# JadePlus_v0_3_1_schematics_PG3_CONN.net
KiCad netlist of a schematic drawn in Altium Designer
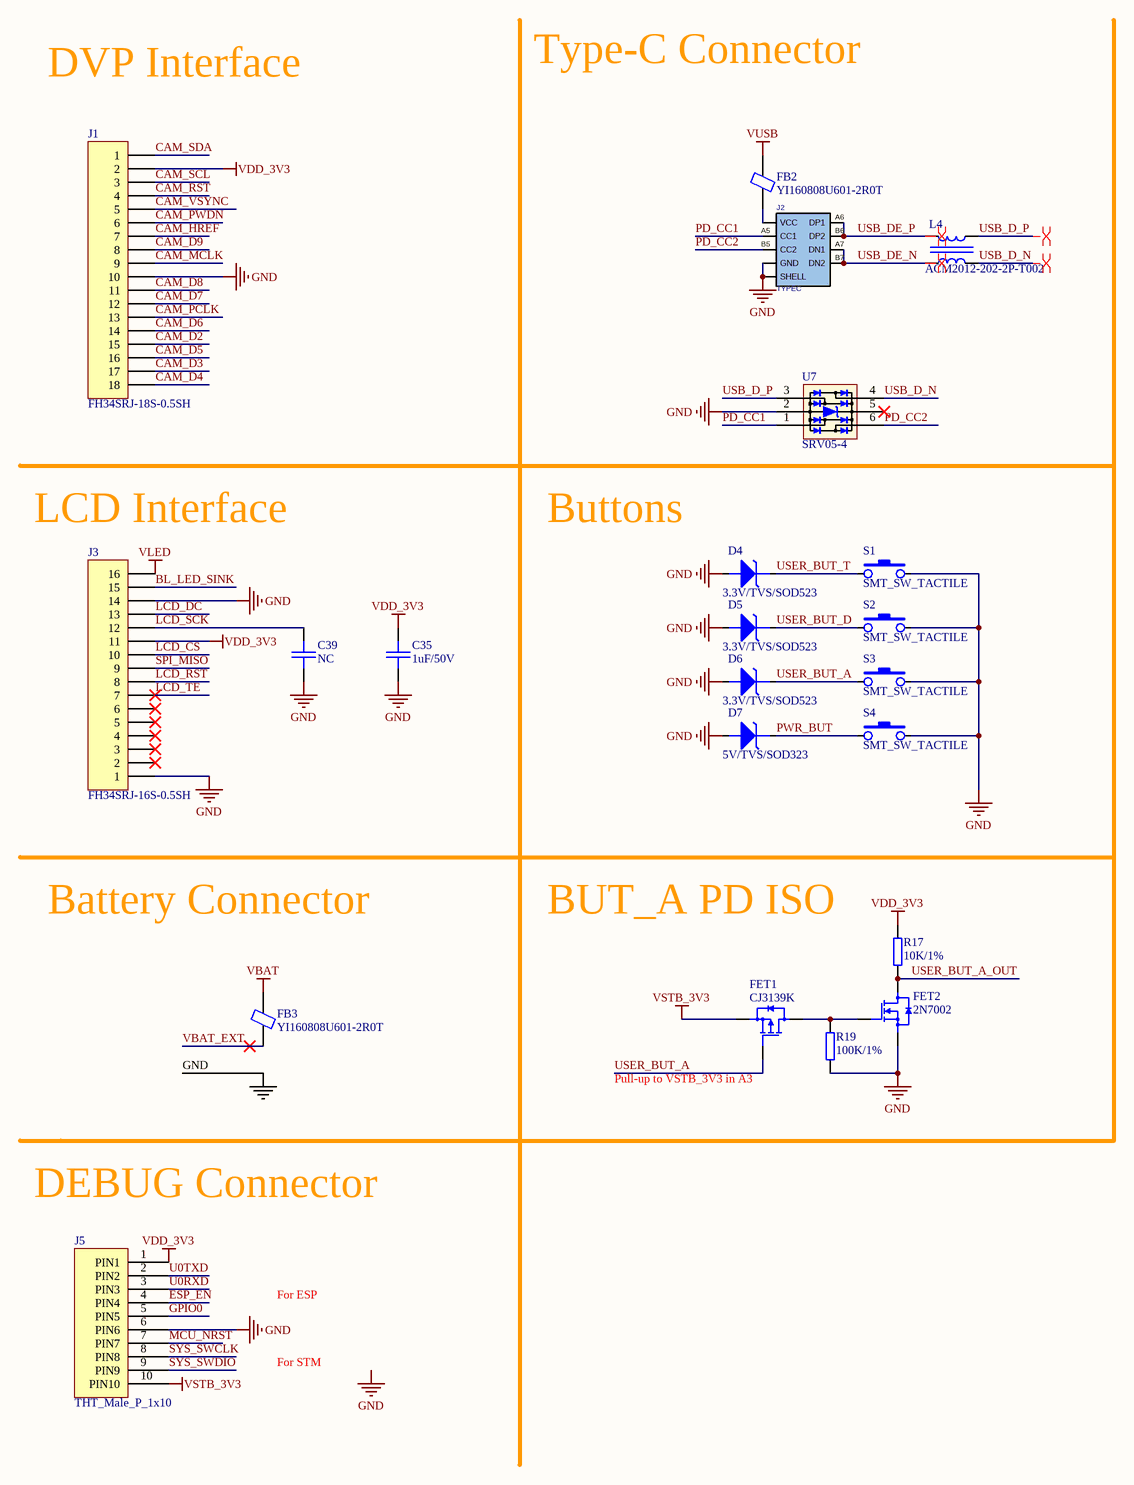
[diagram p0: JadePlus_v0.3.1_schematics_PG3_CONN.SchDoc]

(export (version "E")
  (design (tool "Eeschema 10.0.6"))
  (components
    (comp (ref "C35")
      (value "1uF/50V")
      (footprint "HD-Components:C0402-L-HD")
      (description "Surface mount capacitor 0402")
      (libsource (lib "Vowstar_Basic_Device") (part "SMT_C_0402"))
    )
    (comp (ref "C39")
      (value "NC")
      (footprint "HD-Components:C0201-HD")
      (description "Surface mount capacitor 0402")
      (libsource (lib "Vowstar_Basic_Device") (part "SMT_C_0402"))
    )
    (comp (ref "D4")
      (value "3.3V/TVS/SOD523")
      (footprint "SMT_DIODE_SOD_523")
      (description "Surface mount unidirectional TVS diode SOD-523(0603) Package")
      (libsource (lib "Vowstar_Basic_Device") (part "SMT_DIODE_TVS_U_SOD_523"))
    )
    (comp (ref "D5")
      (value "3.3V/TVS/SOD523")
      (footprint "SMT_DIODE_SOD_523")
      (description "Surface mount unidirectional TVS diode SOD-523(0603) Package")
      (libsource (lib "Vowstar_Basic_Device") (part "SMT_DIODE_TVS_U_SOD_523"))
    )
    (comp (ref "D6")
      (value "3.3V/TVS/SOD523")
      (footprint "SMT_DIODE_SOD_523")
      (description "Surface mount unidirectional TVS diode SOD-523(0603) Package")
      (libsource (lib "Vowstar_Basic_Device") (part "SMT_DIODE_TVS_U_SOD_523"))
    )
    (comp (ref "D7")
      (value "5V/TVS/SOD323")
      (footprint "SMT_DIODE_SOD_323")
      (description "Surface mount unidirectional TVS diode SOD-523(0603) Package")
      (libsource (lib "Vowstar_Basic_Device") (part "SMT_DIODE_TVS_U_SOD_523"))
    )
    (comp (ref "FB2")
      (value "YI160808U601-2R0T")
      (footprint "L0603-HD")
      (description "Surface mount ferrite beads 0603")
      (libsource (lib "Vowstar_Basic_Device") (part "SMT_FB_0603"))
    )
    (comp (ref "FB3")
      (value "YI160808U601-2R0T")
      (footprint "L0603-HD")
      (description "Surface mount ferrite beads 0603")
      (libsource (lib "Vowstar_Basic_Device") (part "SMT_FB_0603"))
    )
    (comp (ref "FET1")
      (value "CJ3139K")
      (footprint "SOT-723-HD")
      (description "SI2301-P-Ch,-2.3A, -20V.RDS(ON) = 0.190Ω @ VGS = -2.5 V")
      (libsource (lib "Vowstar_Basic_Device") (part "SI2301-P-Ch-MOSFET"))
    )
    (comp (ref "FET2")
      (value "2N7002")
      (footprint "SOT-723-HD")
      (description "SI2302-N-Ch,3A, 20V.RDS(ON) = 0.082Ω @ VGS = 2.5 V")
      (libsource (lib "Vowstar_Basic_Device") (part "SI2302-N-Ch-MOSFET"))
    )
    (comp (ref "J1")
      (value "FH34SRJ-18S-0.5SH")
      (footprint "FH34SRJ-18S-0.5SH")
      (description "Header, 18-Pin")
      (fields (field (name "PUBLISHER") "Altium Limited"))
      (libsource (lib "Miscellaneous Connectors") (part "Header 18"))
    )
    (comp (ref "J2")
      (value "TYPEC")
      (footprint "USB_TYPEC_16P_HD")
      (libsource (lib "LibMySelf_SCHLIB") (part "USB_TYPEC_16P"))
    )
    (comp (ref "J3")
      (value "FH34SRJ-16S-0.5SH")
      (footprint "FPC_0.5MM_16P_H1.0_DNUP_FH34SRJ-16S-0.5SH")
      (description "Header, 16-Pin")
      (fields (field (name "PUBLISHER") "Altium Limited"))
      (libsource (lib "Miscellaneous Connectors") (part "Header 16"))
    )
    (comp (ref "J5")
      (value "THT_Male_P_1x10")
      (footprint "THT_Male_P_1x10-2.54mm")
      (description "THT Male pin header strip 1x10")
      (libsource (lib "Vowstar_Connector") (part "THT_Male_P_1x10"))
    )
    (comp (ref "L4")
      (value "ACM2012-202-2P-T002")
      (footprint "ACM2012")
      (libsource (lib "GENERAL-IC") (part "ACM2012"))
    )
    (comp (ref "R17")
      (value "10K/1%")
      (footprint "R0402-HD")
      (description "Surface mount resistor 0402")
      (libsource (lib "Vowstar_Basic_Device") (part "SMT_R_0402"))
    )
    (comp (ref "R19")
      (value "100K/1%")
      (footprint "R0402-HD")
      (description "Surface mount resistor 0402")
      (libsource (lib "Vowstar_Basic_Device") (part "SMT_R_0402"))
    )
    (comp (ref "S1")
      (value "SMT_SW_TACTILE")
      (footprint "SMT_SW_TS_1186D_C_A")
      (description "Generic SMT Tactile Switch")
      (libsource (lib "Vowstar_Switch") (part "SMT_SW_TACTILE"))
    )
    (comp (ref "S2")
      (value "SMT_SW_TACTILE")
      (footprint "SMT_SW_TS_1186D_C_A")
      (description "Generic SMT Tactile Switch")
      (libsource (lib "Vowstar_Switch") (part "SMT_SW_TACTILE"))
    )
    (comp (ref "S3")
      (value "SMT_SW_TACTILE")
      (footprint "SMT_SW_PTS_820")
      (description "Generic SMT Tactile Switch")
      (libsource (lib "Vowstar_Switch") (part "SMT_SW_TACTILE"))
    )
    (comp (ref "S4")
      (value "SMT_SW_TACTILE")
      (footprint "SMT_SW_TS_1186D_C_A")
      (description "Generic SMT Tactile Switch")
      (libsource (lib "Vowstar_Switch") (part "SMT_SW_TACTILE"))
    )
    (comp (ref "U7")
      (value "SRV05-4")
      (footprint "SOT-236-HD")
      (description "Low Capacitance(3pF) TVS Diode Array")
      (libsource (lib "Vowstar_IC_General") (part "SRV05-4"))
    )
  )
  (nets
    (net (code "1") (name "/BL_LED_SINK") (class "Default")
      (node (ref "J3") (pin "15") (pinfunction "15_15") (pintype "passive"))
    )
    (net (code "2") (name "/CAM_D2") (class "Default")
      (node (ref "J1") (pin "15") (pinfunction "15_15") (pintype "passive"))
    )
    (net (code "3") (name "/CAM_D3") (class "Default")
      (node (ref "J1") (pin "17") (pinfunction "17_17") (pintype "passive"))
    )
    (net (code "4") (name "/CAM_D4") (class "Default")
      (node (ref "J1") (pin "18") (pinfunction "18_18") (pintype "passive"))
    )
    (net (code "5") (name "/CAM_D5") (class "Default")
      (node (ref "J1") (pin "16") (pinfunction "16_16") (pintype "passive"))
    )
    (net (code "6") (name "/CAM_D6") (class "Default")
      (node (ref "J1") (pin "14") (pinfunction "14_14") (pintype "passive"))
    )
    (net (code "7") (name "/CAM_D7") (class "Default")
      (node (ref "J1") (pin "12") (pinfunction "12_12") (pintype "passive"))
    )
    (net (code "8") (name "/CAM_D8") (class "Default")
      (node (ref "J1") (pin "11") (pinfunction "11_11") (pintype "passive"))
    )
    (net (code "9") (name "/CAM_D9") (class "Default")
      (node (ref "J1") (pin "8") (pinfunction "8_8") (pintype "passive"))
    )
    (net (code "10") (name "/CAM_HREF") (class "Default")
      (node (ref "J1") (pin "7") (pinfunction "7_7") (pintype "passive"))
    )
    (net (code "11") (name "/CAM_MCLK") (class "Default")
      (node (ref "J1") (pin "9") (pinfunction "9_9") (pintype "passive"))
    )
    (net (code "12") (name "/CAM_PCLK") (class "Default")
      (node (ref "J1") (pin "13") (pinfunction "13_13") (pintype "passive"))
    )
    (net (code "13") (name "/CAM_PWDN") (class "Default")
      (node (ref "J1") (pin "6") (pinfunction "6_6") (pintype "passive"))
    )
    (net (code "14") (name "/CAM_RST") (class "Default")
      (node (ref "J1") (pin "4") (pinfunction "4_4") (pintype "passive"))
    )
    (net (code "15") (name "/CAM_SCL") (class "Default")
      (node (ref "J1") (pin "3") (pinfunction "3_3") (pintype "passive"))
    )
    (net (code "16") (name "/CAM_SDA") (class "Default")
      (node (ref "J1") (pin "1") (pinfunction "1_1") (pintype "passive"))
    )
    (net (code "17") (name "/CAM_VSYNC") (class "Default")
      (node (ref "J1") (pin "5") (pinfunction "5_5") (pintype "passive"))
    )
    (net (code "18") (name "/ESP_EN") (class "Default")
      (node (ref "J5") (pin "4") (pinfunction "PIN4_4") (pintype "passive"))
    )
    (net (code "19") (name "/GPIO0") (class "Default")
      (node (ref "J5") (pin "5") (pinfunction "PIN5_5") (pintype "passive"))
    )
    (net (code "20") (name "/LCD_CS") (class "Default")
      (node (ref "J3") (pin "10") (pinfunction "10_10") (pintype "passive"))
    )
    (net (code "21") (name "/LCD_DC") (class "Default")
      (node (ref "J3") (pin "13") (pinfunction "13_13") (pintype "passive"))
    )
    (net (code "22") (name "/LCD_RST") (class "Default")
      (node (ref "J3") (pin "8") (pinfunction "8_8") (pintype "passive"))
    )
    (net (code "23") (name "/LCD_SCK") (class "Default")
      (node (ref "C39") (pin "1") (pinfunction "1_1") (pintype "passive"))
      (node (ref "J3") (pin "12") (pinfunction "12_12") (pintype "passive"))
    )
    (net (code "24") (name "/LCD_TE") (class "Default")
      (node (ref "J3") (pin "7") (pinfunction "7_7") (pintype "passive+no_connect"))
    )
    (net (code "25") (name "/MCU_NRST") (class "Default")
      (node (ref "J5") (pin "7") (pinfunction "PIN7_7") (pintype "passive"))
    )
    (net (code "26") (name "/PD_CC1") (class "Default")
      (node (ref "J2") (pin "A5") (pinfunction "CC1_A5") (pintype "passive"))
      (node (ref "U7") (pin "1") (pintype "passive"))
    )
    (net (code "27") (name "/PD_CC2") (class "Default")
      (node (ref "J2") (pin "B5") (pinfunction "CC2_B5") (pintype "passive"))
      (node (ref "U7") (pin "6") (pintype "passive"))
    )
    (net (code "28") (name "/PWR_BUT") (class "Default")
      (node (ref "D7") (pin "2") (pinfunction "K_2") (pintype "passive"))
      (node (ref "S4") (pin "1") (pinfunction "1_1") (pintype "passive"))
    )
    (net (code "29") (name "/SPI_MISO") (class "Default")
      (node (ref "J3") (pin "9") (pinfunction "9_9") (pintype "passive"))
    )
    (net (code "30") (name "/SYS_SWCLK") (class "Default")
      (node (ref "J5") (pin "8") (pinfunction "PIN8_8") (pintype "passive"))
    )
    (net (code "31") (name "/SYS_SWDIO") (class "Default")
      (node (ref "J5") (pin "9") (pinfunction "PIN9_9") (pintype "passive"))
    )
    (net (code "32") (name "/U0RXD") (class "Default")
      (node (ref "J5") (pin "3") (pinfunction "PIN3_3") (pintype "passive"))
    )
    (net (code "33") (name "/U0TXD") (class "Default")
      (node (ref "J5") (pin "2") (pinfunction "PIN2_2") (pintype "passive"))
    )
    (net (code "34") (name "/USB_DE_N") (class "Default")
      (node (ref "J2") (pin "A7") (pinfunction "DN1_A7") (pintype "passive"))
      (node (ref "J2") (pin "B7") (pinfunction "DN2_B7") (pintype "passive"))
      (node (ref "L4") (pin "2") (pinfunction "2_2") (pintype "passive"))
    )
    (net (code "35") (name "/USB_DE_P") (class "Default")
      (node (ref "J2") (pin "A6") (pinfunction "DP1_A6") (pintype "passive"))
      (node (ref "J2") (pin "B6") (pinfunction "DP2_B6") (pintype "passive"))
      (node (ref "L4") (pin "1") (pinfunction "1_1") (pintype "passive"))
    )
    (net (code "36") (name "/USB_D_N") (class "Default")
      (node (ref "L4") (pin "3") (pinfunction "3_3") (pintype "passive"))
      (node (ref "U7") (pin "4") (pintype "passive"))
    )
    (net (code "37") (name "/USB_D_P") (class "Default")
      (node (ref "L4") (pin "4") (pinfunction "4_4") (pintype "passive"))
      (node (ref "U7") (pin "3") (pintype "passive"))
    )
    (net (code "38") (name "/USER_BUT_A") (class "Default")
      (node (ref "D6") (pin "2") (pinfunction "K_2") (pintype "passive"))
      (node (ref "FET1") (pin "1") (pinfunction "G_1") (pintype "passive"))
      (node (ref "S3") (pin "1") (pinfunction "1_1") (pintype "passive"))
    )
    (net (code "39") (name "/USER_BUT_A_OUT") (class "Default")
      (node (ref "FET2") (pin "3") (pinfunction "D_3") (pintype "passive"))
      (node (ref "R17") (pin "2") (pinfunction "2_2") (pintype "passive"))
    )
    (net (code "40") (name "/USER_BUT_D") (class "Default")
      (node (ref "D5") (pin "2") (pinfunction "K_2") (pintype "passive"))
      (node (ref "S2") (pin "1") (pinfunction "1_1") (pintype "passive"))
    )
    (net (code "41") (name "/USER_BUT_T") (class "Default")
      (node (ref "D4") (pin "2") (pinfunction "K_2") (pintype "passive"))
      (node (ref "S1") (pin "1") (pinfunction "1_1") (pintype "passive"))
    )
    (net (code "42") (name "/VBAT_EXT") (class "Default")
      (node (ref "FB3") (pin "2") (pinfunction "2_2") (pintype "passive"))
    )
    (net (code "43") (name "GND") (class "Default")
      (node (ref "C35") (pin "1") (pinfunction "1_1") (pintype "passive"))
      (node (ref "C39") (pin "2") (pinfunction "2_2") (pintype "passive"))
      (node (ref "D4") (pin "1") (pinfunction "A_1") (pintype "passive"))
      (node (ref "D5") (pin "1") (pinfunction "A_1") (pintype "passive"))
      (node (ref "D6") (pin "1") (pinfunction "A_1") (pintype "passive"))
      (node (ref "D7") (pin "1") (pinfunction "A_1") (pintype "passive"))
      (node (ref "FET2") (pin "2") (pinfunction "S_2") (pintype "passive"))
      (node (ref "J1") (pin "10") (pinfunction "10_10") (pintype "passive"))
      (node (ref "J2") (pin "GND") (pinfunction "GND_GND") (pintype "passive"))
      (node (ref "J2") (pin "SHELL") (pinfunction "SHELL_SHELL") (pintype "passive"))
      (node (ref "J3") (pin "1") (pinfunction "1_1") (pintype "passive"))
      (node (ref "J3") (pin "14") (pinfunction "14_14") (pintype "passive"))
      (node (ref "J5") (pin "6") (pinfunction "PIN6_6") (pintype "passive"))
      (node (ref "R19") (pin "2") (pinfunction "2_2") (pintype "passive"))
      (node (ref "S1") (pin "2") (pinfunction "2_2") (pintype "passive"))
      (node (ref "S2") (pin "2") (pinfunction "2_2") (pintype "passive"))
      (node (ref "S3") (pin "2") (pinfunction "2_2") (pintype "passive"))
      (node (ref "S4") (pin "2") (pinfunction "2_2") (pintype "passive"))
      (node (ref "U7") (pin "2") (pintype "passive"))
    )
    (net (code "44") (name "Net-(FET1-D)") (class "Default")
      (node (ref "FET1") (pin "3") (pinfunction "D_3") (pintype "passive"))
      (node (ref "FET2") (pin "1") (pinfunction "G_1") (pintype "passive"))
      (node (ref "R19") (pin "1") (pinfunction "1_1") (pintype "passive"))
    )
    (net (code "45") (name "Net-(J2-VCC)") (class "Default")
      (node (ref "FB2") (pin "2") (pinfunction "2_2") (pintype "passive"))
      (node (ref "J2") (pin "VBUS") (pinfunction "VCC_VBUS") (pintype "passive"))
    )
    (net (code "46") (name "VBAT") (class "Default")
      (node (ref "FB3") (pin "1") (pinfunction "1_1") (pintype "passive"))
    )
    (net (code "47") (name "VDD_3V3") (class "Default")
      (node (ref "C35") (pin "2") (pinfunction "2_2") (pintype "passive"))
      (node (ref "J1") (pin "2") (pinfunction "2_2") (pintype "passive"))
      (node (ref "J3") (pin "11") (pinfunction "11_11") (pintype "passive"))
      (node (ref "J5") (pin "1") (pinfunction "PIN1_1") (pintype "passive"))
      (node (ref "R17") (pin "1") (pinfunction "1_1") (pintype "passive"))
    )
    (net (code "48") (name "VLED") (class "Default")
      (node (ref "J3") (pin "16") (pinfunction "16_16") (pintype "passive"))
    )
    (net (code "49") (name "VSTB_3V3") (class "Default")
      (node (ref "FET1") (pin "2") (pinfunction "S_2") (pintype "passive"))
      (node (ref "J5") (pin "10") (pinfunction "PIN10_10") (pintype "passive"))
    )
    (net (code "50") (name "VUSB") (class "Default")
      (node (ref "FB2") (pin "1") (pinfunction "1_1") (pintype "passive"))
    )
    (net (code "51") (name "unconnected-(J3-Pad2)") (class "Default")
      (node (ref "J3") (pin "2") (pinfunction "2_2") (pintype "passive+no_connect"))
    )
    (net (code "52") (name "unconnected-(J3-Pad3)") (class "Default")
      (node (ref "J3") (pin "3") (pinfunction "3_3") (pintype "passive+no_connect"))
    )
    (net (code "53") (name "unconnected-(J3-Pad4)") (class "Default")
      (node (ref "J3") (pin "4") (pinfunction "4_4") (pintype "passive+no_connect"))
    )
    (net (code "54") (name "unconnected-(J3-Pad5)") (class "Default")
      (node (ref "J3") (pin "5") (pinfunction "5_5") (pintype "passive+no_connect"))
    )
    (net (code "55") (name "unconnected-(J3-Pad6)") (class "Default")
      (node (ref "J3") (pin "6") (pinfunction "6_6") (pintype "passive+no_connect"))
    )
    (net (code "56") (name "unconnected-(U7-Pad5)") (class "Default")
      (node (ref "U7") (pin "5") (pintype "passive+no_connect"))
    )
  )
)
